# SCH_Schematic_Smart-agriculture-monitori.net
KiCad netlist of a schematic drawn in EasyEDA
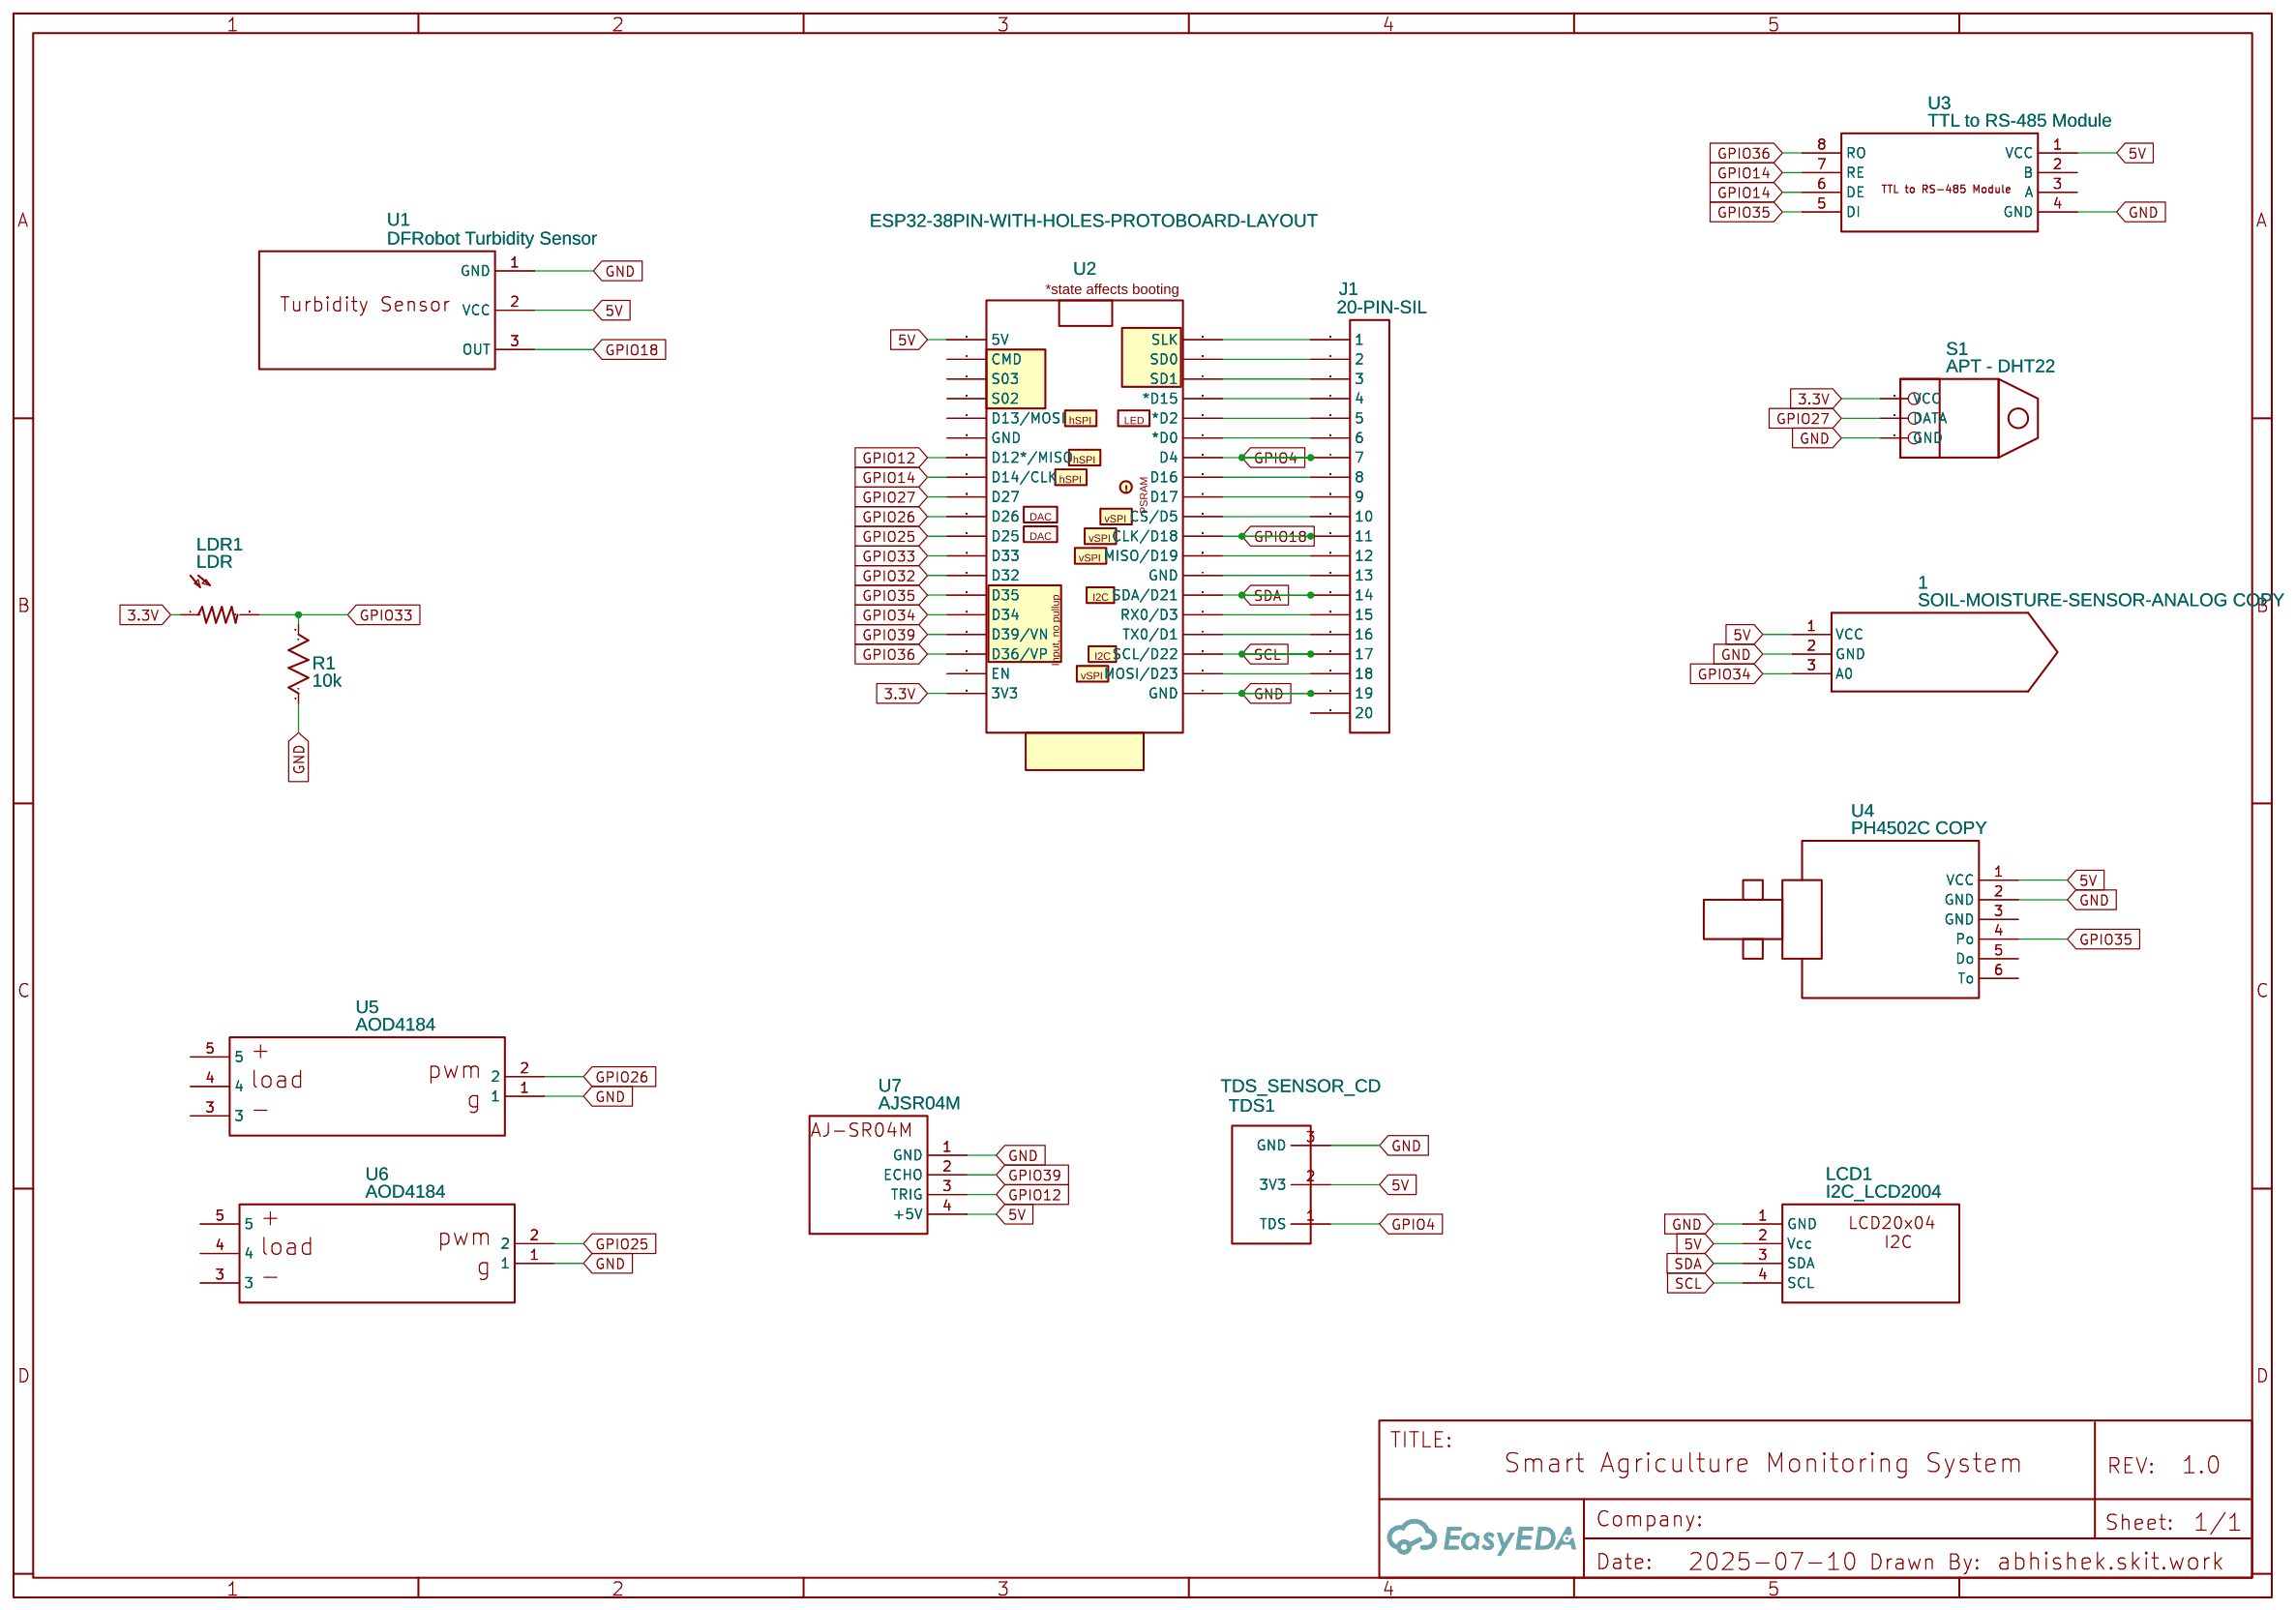
[diagram p0: schematic sheet]

(export (version "E")
  (design (tool "Eeschema 10.0.6"))
  (components
    (comp (ref "1")
      (value "SOIL-MOISTURE-SENSOR-ANALOG COPY")
      (libsource (lib "") (part "SOIL-MOISTURE-SENSOR-ANALOG COPY"))
    )
    (comp (ref "J1") (value "20-PIN-SIL") (libsource (lib "") (part "20-PIN-SIL")))
    (comp (ref "LCD1")
      (value "I2C_LCD2004")
      (fields (field (name "Manufacturer") "Various"))
      (libsource (lib "") (part "I2C_LCD2004"))
    )
    (comp (ref "LDR1") (value "LDR") (libsource (lib "") (part "LDR")))
    (comp (ref "R1") (value "10k") (libsource (lib "") (part "R_0805_US")))
    (comp (ref "S1") (value "APT - DHT22") (libsource (lib "") (part "APT - DHT22")))
    (comp (ref "TDS1") (value "TDS_SENSOR_CD") (libsource (lib "") (part "TDS_SENSOR_CD")))
    (comp (ref "U1")
      (value "DFRobot Turbidity Sensor")
      (libsource (lib "") (part "DFRobot Turbidity Sensor"))
    )
    (comp (ref "U2")
      (value "ESP32-38PIN-WITH-HOLES-PROTOBOARD-LAYOUT")
      (libsource (lib "") (part "ESP32-38PIN-WITH-HOLES-PROTOBOARD-LAYOUT"))
    )
    (comp (ref "U3") (value "TTL to RS-485 Module") (libsource (lib "") (part "TTL to RS-485 Module")))
    (comp (ref "U4")
      (value "PH4502C COPY")
      (fields (field (name "Manufacturer Part") "Pre-Assembled Female BNC"))
      (libsource (lib "") (part "PH4502C COPY"))
    )
    (comp (ref "U5") (value "AOD4184") (libsource (lib "") (part "AOD4184")))
    (comp (ref "U6") (value "AOD4184") (libsource (lib "") (part "AOD4184")))
    (comp (ref "U7") (value "AJSR04M") (libsource (lib "") (part "AJSR04M")))
  )
  (nets
    (net (code "1") (name "3.3V") (class "Default")
      (node (ref "LDR1") (pin "1") (pinfunction "1_1") (pintype "bidirectional"))
      (node (ref "S1") (pin "1") (pinfunction "VCC_1") (pintype "unspecified"))
      (node (ref "U2") (pin "38") (pinfunction "3V3_38") (pintype "unspecified"))
    )
    (net (code "2") (name "5V") (class "Default")
      (node (ref "1") (pin "1") (pinfunction "VCC_1") (pintype "bidirectional"))
      (node (ref "LCD1") (pin "2") (pinfunction "Vcc_2") (pintype "unspecified"))
      (node (ref "TDS1") (pin "2") (pinfunction "3V3_2") (pintype "unspecified"))
      (node (ref "U1") (pin "2") (pinfunction "VCC_2") (pintype "unspecified"))
      (node (ref "U2") (pin "20") (pinfunction "5V_20") (pintype "unspecified"))
      (node (ref "U3") (pin "1") (pinfunction "VCC_1") (pintype "unspecified"))
      (node (ref "U4") (pin "1") (pinfunction "VCC_1") (pintype "unspecified"))
      (node (ref "U7") (pin "4") (pinfunction "+5V_4") (pintype "unspecified"))
    )
    (net (code "3") (name "GND") (class "Default")
      (node (ref "1") (pin "2") (pinfunction "GND_2") (pintype "bidirectional"))
      (node (ref "J1") (pin "19") (pinfunction "19_19") (pintype "unspecified"))
      (node (ref "LCD1") (pin "1") (pinfunction "GND_1") (pintype "unspecified"))
      (node (ref "R1") (pin "1") (pinfunction "1_1") (pintype "unspecified"))
      (node (ref "S1") (pin "3") (pinfunction "GND_3") (pintype "unspecified"))
      (node (ref "TDS1") (pin "3") (pinfunction "GND_3") (pintype "unspecified"))
      (node (ref "U1") (pin "1") (pinfunction "GND_1") (pintype "unspecified"))
      (node (ref "U2") (pin "1") (pinfunction "GND_1") (pintype "unspecified"))
      (node (ref "U3") (pin "4") (pinfunction "GND_4") (pintype "unspecified"))
      (node (ref "U4") (pin "2") (pinfunction "GND_2") (pintype "unspecified"))
      (node (ref "U5") (pin "1") (pinfunction "1_1") (pintype "unspecified"))
      (node (ref "U6") (pin "1") (pinfunction "1_1") (pintype "unspecified"))
      (node (ref "U7") (pin "1") (pinfunction "GND_1") (pintype "unspecified"))
    )
    (net (code "4") (name "GPIO4") (class "Default")
      (node (ref "J1") (pin "7") (pinfunction "7_7") (pintype "unspecified"))
      (node (ref "TDS1") (pin "1") (pinfunction "TDS_1") (pintype "unspecified"))
      (node (ref "U2") (pin "13") (pinfunction "D4_13") (pintype "unspecified"))
    )
    (net (code "5") (name "GPIO12") (class "Default")
      (node (ref "U2") (pin "26") (pinfunction "D12*/MISO_26") (pintype "unspecified"))
      (node (ref "U7") (pin "3") (pinfunction "TRIG_3") (pintype "unspecified"))
    )
    (net (code "6") (name "GPIO14") (class "Default")
      (node (ref "U2") (pin "27") (pinfunction "D14/CLK_27") (pintype "unspecified"))
      (node (ref "U3") (pin "6") (pinfunction "DE_6") (pintype "unspecified"))
      (node (ref "U3") (pin "7") (pinfunction "RE_7") (pintype "unspecified"))
    )
    (net (code "7") (name "GPIO18") (class "Default")
      (node (ref "J1") (pin "11") (pinfunction "11_11") (pintype "unspecified"))
      (node (ref "U1") (pin "3") (pinfunction "OUT_3") (pintype "unspecified"))
      (node (ref "U2") (pin "9") (pinfunction "CLK/D18_9") (pintype "unspecified"))
    )
    (net (code "8") (name "GPIO25") (class "Default")
      (node (ref "U2") (pin "30") (pinfunction "D25_30") (pintype "unspecified"))
      (node (ref "U6") (pin "2") (pinfunction "2_2") (pintype "unspecified"))
    )
    (net (code "9") (name "GPIO26") (class "Default")
      (node (ref "U2") (pin "29") (pinfunction "D26_29") (pintype "unspecified"))
      (node (ref "U5") (pin "2") (pinfunction "2_2") (pintype "unspecified"))
    )
    (net (code "10") (name "GPIO27") (class "Default")
      (node (ref "S1") (pin "2") (pinfunction "DATA_2") (pintype "unspecified"))
      (node (ref "U2") (pin "28") (pinfunction "D27_28") (pintype "unspecified"))
    )
    (net (code "11") (name "GPIO32") (class "Default")
      (node (ref "U2") (pin "32") (pinfunction "D32_32") (pintype "unspecified"))
    )
    (net (code "12") (name "GPIO33") (class "Default")
      (node (ref "LDR1") (pin "2") (pinfunction "2_2") (pintype "bidirectional"))
      (node (ref "R1") (pin "2") (pinfunction "2_2") (pintype "unspecified"))
      (node (ref "U2") (pin "31") (pinfunction "D33_31") (pintype "unspecified"))
    )
    (net (code "13") (name "GPIO34") (class "Default")
      (node (ref "1") (pin "3") (pinfunction "A0_3") (pintype "bidirectional"))
      (node (ref "U2") (pin "34") (pinfunction "D34_34") (pintype "unspecified"))
    )
    (net (code "14") (name "GPIO35") (class "Default")
      (node (ref "U2") (pin "33") (pinfunction "D35_33") (pintype "unspecified"))
      (node (ref "U3") (pin "5") (pinfunction "DI_5") (pintype "unspecified"))
      (node (ref "U4") (pin "4") (pinfunction "Po_4") (pintype "unspecified"))
    )
    (net (code "15") (name "GPIO36") (class "Default")
      (node (ref "U2") (pin "36") (pinfunction "D36/VP_36") (pintype "unspecified"))
      (node (ref "U3") (pin "8") (pinfunction "RO_8") (pintype "unspecified"))
    )
    (net (code "16") (name "GPIO39") (class "Default")
      (node (ref "U2") (pin "35") (pinfunction "D39/VN_35") (pintype "unspecified"))
      (node (ref "U7") (pin "2") (pinfunction "ECHO_2") (pintype "unspecified"))
    )
    (net (code "17") (name "Net-(J1-Pad13)") (class "Default")
      (node (ref "J1") (pin "13") (pinfunction "13_13") (pintype "unspecified"))
      (node (ref "U2") (pin "7") (pinfunction "GND_7") (pintype "unspecified"))
    )
    (net (code "18") (name "Net-(U2-*D0)") (class "Default")
      (node (ref "J1") (pin "6") (pinfunction "6_6") (pintype "unspecified"))
      (node (ref "U2") (pin "14") (pinfunction "*D0_14") (pintype "unspecified"))
    )
    (net (code "19") (name "Net-(U2-*D2)") (class "Default")
      (node (ref "J1") (pin "5") (pinfunction "5_5") (pintype "unspecified"))
      (node (ref "U2") (pin "15") (pinfunction "*D2_15") (pintype "unspecified"))
    )
    (net (code "20") (name "Net-(U2-*D15)") (class "Default")
      (node (ref "J1") (pin "4") (pinfunction "4_4") (pintype "unspecified"))
      (node (ref "U2") (pin "16") (pinfunction "*D15_16") (pintype "unspecified"))
    )
    (net (code "21") (name "Net-(U2-CS{slash}D5)") (class "Default")
      (node (ref "J1") (pin "10") (pinfunction "10_10") (pintype "unspecified"))
      (node (ref "U2") (pin "10") (pinfunction "CS/D5_10") (pintype "unspecified"))
    )
    (net (code "22") (name "Net-(U2-D16)") (class "Default")
      (node (ref "J1") (pin "8") (pinfunction "8_8") (pintype "unspecified"))
      (node (ref "U2") (pin "12") (pinfunction "D16_12") (pintype "unspecified"))
    )
    (net (code "23") (name "Net-(U2-D17)") (class "Default")
      (node (ref "J1") (pin "9") (pinfunction "9_9") (pintype "unspecified"))
      (node (ref "U2") (pin "11") (pinfunction "D17_11") (pintype "unspecified"))
    )
    (net (code "24") (name "Net-(U2-MISO{slash}D19)") (class "Default")
      (node (ref "J1") (pin "12") (pinfunction "12_12") (pintype "unspecified"))
      (node (ref "U2") (pin "8") (pinfunction "MISO/D19_8") (pintype "unspecified"))
    )
    (net (code "25") (name "Net-(U2-MOSI{slash}D23)") (class "Default")
      (node (ref "J1") (pin "18") (pinfunction "18_18") (pintype "unspecified"))
      (node (ref "U2") (pin "2") (pinfunction "MOSI/D23_2") (pintype "unspecified"))
    )
    (net (code "26") (name "Net-(U2-RX0{slash}D3)") (class "Default")
      (node (ref "J1") (pin "15") (pinfunction "15_15") (pintype "unspecified"))
      (node (ref "U2") (pin "5") (pinfunction "RX0/D3_5") (pintype "unspecified"))
    )
    (net (code "27") (name "Net-(U2-SD0)") (class "Default")
      (node (ref "J1") (pin "2") (pinfunction "2_2") (pintype "unspecified"))
      (node (ref "U2") (pin "18") (pinfunction "SD0_18") (pintype "unspecified"))
    )
    (net (code "28") (name "Net-(U2-SD1)") (class "Default")
      (node (ref "J1") (pin "3") (pinfunction "3_3") (pintype "unspecified"))
      (node (ref "U2") (pin "17") (pinfunction "SD1_17") (pintype "unspecified"))
    )
    (net (code "29") (name "Net-(U2-SLK)") (class "Default")
      (node (ref "J1") (pin "1") (pinfunction "1_1") (pintype "unspecified"))
      (node (ref "U2") (pin "19") (pinfunction "SLK_19") (pintype "unspecified"))
    )
    (net (code "30") (name "Net-(U2-TX0{slash}D1)") (class "Default")
      (node (ref "J1") (pin "16") (pinfunction "16_16") (pintype "unspecified"))
      (node (ref "U2") (pin "4") (pinfunction "TX0/D1_4") (pintype "unspecified"))
    )
    (net (code "31") (name "SCL") (class "Default")
      (node (ref "J1") (pin "17") (pinfunction "17_17") (pintype "unspecified"))
      (node (ref "LCD1") (pin "4") (pinfunction "SCL_4") (pintype "unspecified"))
      (node (ref "U2") (pin "3") (pinfunction "SCL/D22_3") (pintype "unspecified"))
    )
    (net (code "32") (name "SDA") (class "Default")
      (node (ref "J1") (pin "14") (pinfunction "14_14") (pintype "unspecified"))
      (node (ref "LCD1") (pin "3") (pinfunction "SDA_3") (pintype "unspecified"))
      (node (ref "U2") (pin "6") (pinfunction "SDA/D21_6") (pintype "unspecified"))
    )
    (net (code "33") (name "unconnected-(J1-Pad20)") (class "Default")
      (node (ref "J1") (pin "20") (pinfunction "20_20") (pintype "unspecified"))
    )
    (net (code "34") (name "unconnected-(U2-CMD-Pad21)") (class "Default")
      (node (ref "U2") (pin "21") (pinfunction "CMD_21") (pintype "unspecified"))
    )
    (net (code "35") (name "unconnected-(U2-D13{slash}MOSI-Pad24)") (class "Default")
      (node (ref "U2") (pin "24") (pinfunction "D13/MOSI_24") (pintype "unspecified"))
    )
    (net (code "36") (name "unconnected-(U2-EN-Pad37)") (class "Default")
      (node (ref "U2") (pin "37") (pinfunction "EN_37") (pintype "unspecified"))
    )
    (net (code "37") (name "unconnected-(U2-GND-Pad25)") (class "Default")
      (node (ref "U2") (pin "25") (pinfunction "GND_25") (pintype "unspecified"))
    )
    (net (code "38") (name "unconnected-(U2-S02-Pad23)") (class "Default")
      (node (ref "U2") (pin "23") (pinfunction "S02_23") (pintype "unspecified"))
    )
    (net (code "39") (name "unconnected-(U2-S03-Pad22)") (class "Default")
      (node (ref "U2") (pin "22") (pinfunction "S03_22") (pintype "unspecified"))
    )
    (net (code "40") (name "unconnected-(U3-A-Pad3)") (class "Default")
      (node (ref "U3") (pin "3") (pinfunction "A_3") (pintype "unspecified"))
    )
    (net (code "41") (name "unconnected-(U3-B-Pad2)") (class "Default")
      (node (ref "U3") (pin "2") (pinfunction "B_2") (pintype "unspecified"))
    )
    (net (code "42") (name "unconnected-(U4-Do-Pad5)") (class "Default")
      (node (ref "U4") (pin "5") (pinfunction "Do_5") (pintype "unspecified"))
    )
    (net (code "43") (name "unconnected-(U4-GND-Pad3)") (class "Default")
      (node (ref "U4") (pin "3") (pinfunction "GND_3") (pintype "unspecified"))
    )
    (net (code "44") (name "unconnected-(U4-To-Pad6)") (class "Default")
      (node (ref "U4") (pin "6") (pinfunction "To_6") (pintype "unspecified"))
    )
    (net (code "45") (name "unconnected-(U5-Pad3)") (class "Default")
      (node (ref "U5") (pin "3") (pinfunction "3_3") (pintype "unspecified"))
    )
    (net (code "46") (name "unconnected-(U5-Pad4)") (class "Default")
      (node (ref "U5") (pin "4") (pinfunction "4_4") (pintype "unspecified"))
    )
    (net (code "47") (name "unconnected-(U5-Pad5)") (class "Default")
      (node (ref "U5") (pin "5") (pinfunction "5_5") (pintype "unspecified"))
    )
    (net (code "48") (name "unconnected-(U6-Pad3)") (class "Default")
      (node (ref "U6") (pin "3") (pinfunction "3_3") (pintype "unspecified"))
    )
    (net (code "49") (name "unconnected-(U6-Pad4)") (class "Default")
      (node (ref "U6") (pin "4") (pinfunction "4_4") (pintype "unspecified"))
    )
    (net (code "50") (name "unconnected-(U6-Pad5)") (class "Default")
      (node (ref "U6") (pin "5") (pinfunction "5_5") (pintype "unspecified"))
    )
  )
)
